# backplane_rev_2.net
KiCad netlist of a schematic drawn in EAGLE
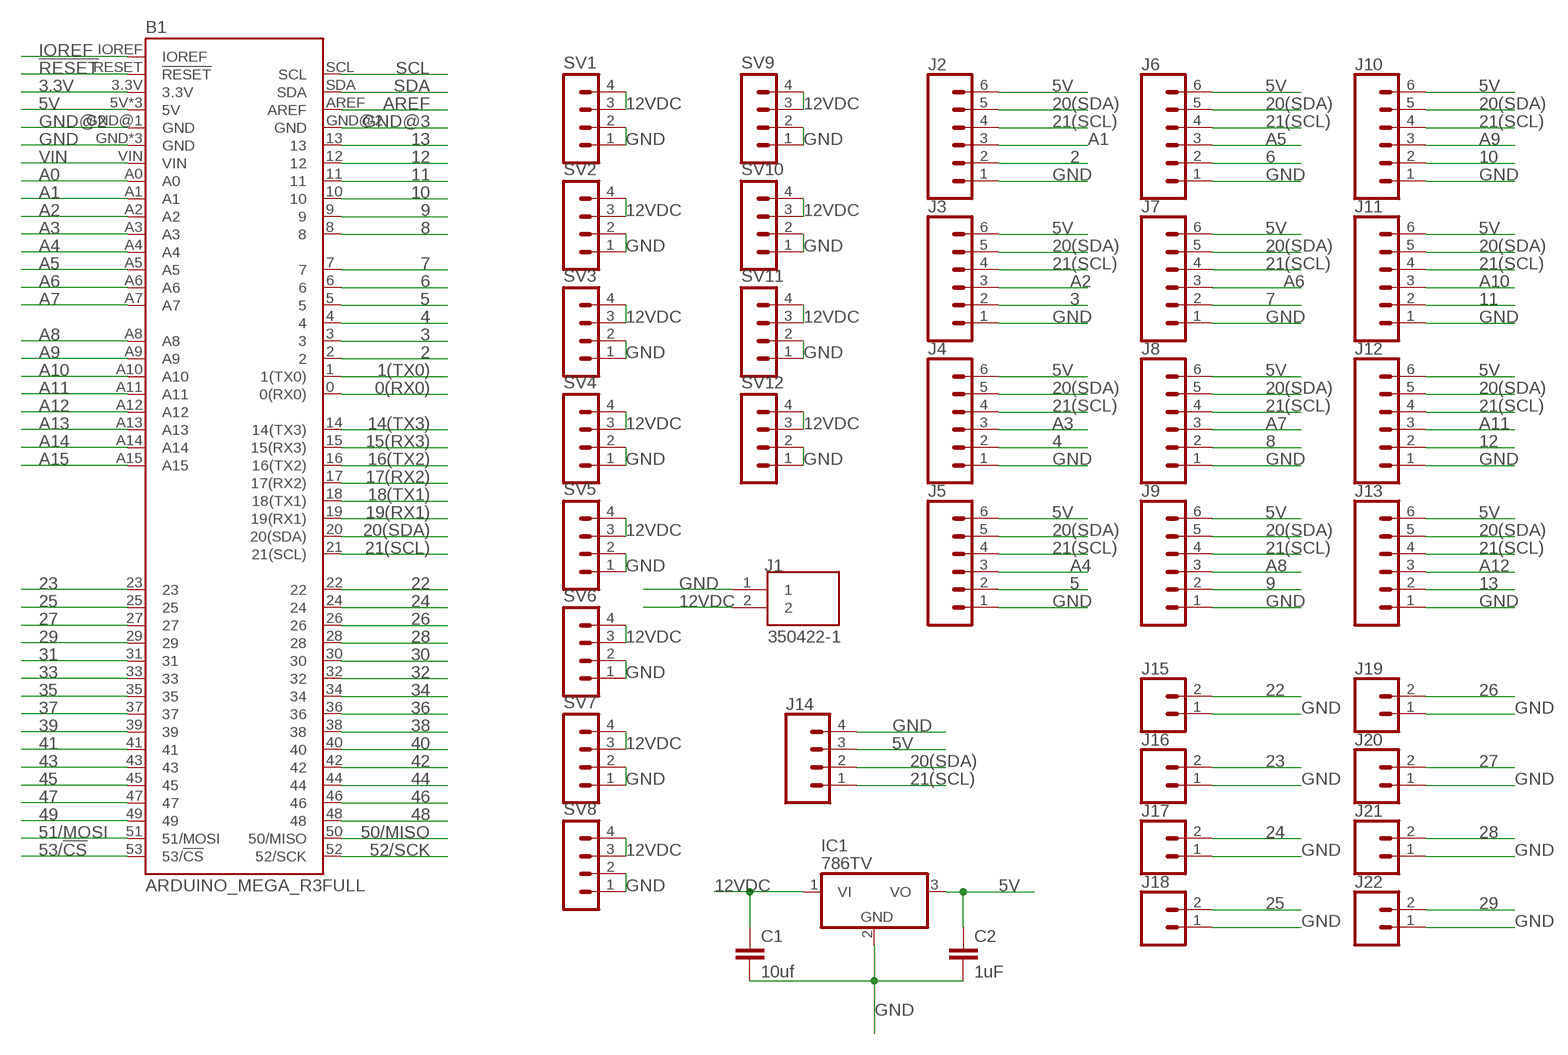
[diagram p0: schematic, sheet 1]

(export (version "E")
  (design (tool "Eeschema 10.0.6"))
  (components
    (comp (ref "B1")
      (value "ARDUINO_MEGA_R3FULL")
      (footprint "eagle-import:ARDUINO_MEGA_NO_SILK")
      (libsource (lib "eagle-import") (part "ARDUINO_MEGA_R3FULL"))
    )
    (comp (ref "C1")
      (value "10uf")
      (footprint "eagle-import:C2.5-3")
      (libsource (lib "eagle-import") (part "C2,5-3"))
    )
    (comp (ref "C2")
      (value "1uF")
      (footprint "eagle-import:C2.5-3")
      (libsource (lib "eagle-import") (part "C2,5-3"))
    )
    (comp (ref "IC1")
      (value "786TV")
      (footprint "eagle-import:TO220V")
      (libsource (lib "eagle-import") (part "78TV6"))
    )
    (comp (ref "J1")
      (value "350422-1")
      (footprint "eagle-import:POWER-PIN")
      (fields (field (name "DIGI-KEY_PART_NUMBER") "A14367-ND") (field (name "MF") "TE Connectivity"))
      (libsource (lib "eagle-import") (part "350422-1"))
    )
    (comp (ref "J2")
      (value "CONN_06NO_SILK_FEMALE_PTH")
      (footprint "eagle-import:1X06_NO_SILK")
      (libsource (lib "eagle-import") (part "CONN_06NO_SILK_FEMALE_PTH"))
    )
    (comp (ref "J3")
      (value "CONN_06NO_SILK_FEMALE_PTH")
      (footprint "eagle-import:1X06_NO_SILK")
      (libsource (lib "eagle-import") (part "CONN_06NO_SILK_FEMALE_PTH"))
    )
    (comp (ref "J4")
      (value "CONN_06NO_SILK_FEMALE_PTH")
      (footprint "eagle-import:1X06_NO_SILK")
      (libsource (lib "eagle-import") (part "CONN_06NO_SILK_FEMALE_PTH"))
    )
    (comp (ref "J5")
      (value "CONN_06NO_SILK_FEMALE_PTH")
      (footprint "eagle-import:1X06_NO_SILK")
      (libsource (lib "eagle-import") (part "CONN_06NO_SILK_FEMALE_PTH"))
    )
    (comp (ref "J6")
      (value "CONN_06NO_SILK_FEMALE_PTH")
      (footprint "eagle-import:1X06_NO_SILK")
      (libsource (lib "eagle-import") (part "CONN_06NO_SILK_FEMALE_PTH"))
    )
    (comp (ref "J7")
      (value "CONN_06NO_SILK_FEMALE_PTH")
      (footprint "eagle-import:1X06_NO_SILK")
      (libsource (lib "eagle-import") (part "CONN_06NO_SILK_FEMALE_PTH"))
    )
    (comp (ref "J8")
      (value "CONN_06NO_SILK_FEMALE_PTH")
      (footprint "eagle-import:1X06_NO_SILK")
      (libsource (lib "eagle-import") (part "CONN_06NO_SILK_FEMALE_PTH"))
    )
    (comp (ref "J9")
      (value "CONN_06NO_SILK_FEMALE_PTH")
      (footprint "eagle-import:1X06_NO_SILK")
      (libsource (lib "eagle-import") (part "CONN_06NO_SILK_FEMALE_PTH"))
    )
    (comp (ref "J10")
      (value "CONN_06NO_SILK_FEMALE_PTH")
      (footprint "eagle-import:1X06_NO_SILK")
      (libsource (lib "eagle-import") (part "CONN_06NO_SILK_FEMALE_PTH"))
    )
    (comp (ref "J11")
      (value "CONN_06NO_SILK_FEMALE_PTH")
      (footprint "eagle-import:1X06_NO_SILK")
      (libsource (lib "eagle-import") (part "CONN_06NO_SILK_FEMALE_PTH"))
    )
    (comp (ref "J12")
      (value "CONN_06NO_SILK_FEMALE_PTH")
      (footprint "eagle-import:1X06_NO_SILK")
      (libsource (lib "eagle-import") (part "CONN_06NO_SILK_FEMALE_PTH"))
    )
    (comp (ref "J13")
      (value "CONN_06NO_SILK_FEMALE_PTH")
      (footprint "eagle-import:1X06_NO_SILK")
      (libsource (lib "eagle-import") (part "CONN_06NO_SILK_FEMALE_PTH"))
    )
    (comp (ref "J14")
      (value "CONN_04PTH")
      (footprint "eagle-import:1X04")
      (libsource (lib "eagle-import") (part "CONN_04PTH"))
    )
    (comp (ref "J15")
      (value "CONN_02")
      (footprint "eagle-import:1X02")
      (libsource (lib "eagle-import") (part "CONN_02"))
    )
    (comp (ref "J16")
      (value "CONN_02")
      (footprint "eagle-import:1X02")
      (libsource (lib "eagle-import") (part "CONN_02"))
    )
    (comp (ref "J17")
      (value "CONN_02")
      (footprint "eagle-import:1X02")
      (libsource (lib "eagle-import") (part "CONN_02"))
    )
    (comp (ref "J18")
      (value "CONN_02")
      (footprint "eagle-import:1X02")
      (libsource (lib "eagle-import") (part "CONN_02"))
    )
    (comp (ref "J19")
      (value "CONN_02")
      (footprint "eagle-import:1X02")
      (libsource (lib "eagle-import") (part "CONN_02"))
    )
    (comp (ref "J20")
      (value "CONN_02")
      (footprint "eagle-import:1X02")
      (libsource (lib "eagle-import") (part "CONN_02"))
    )
    (comp (ref "J21")
      (value "CONN_02")
      (footprint "eagle-import:1X02")
      (libsource (lib "eagle-import") (part "CONN_02"))
    )
    (comp (ref "J22")
      (value "CONN_02")
      (footprint "eagle-import:1X02")
      (libsource (lib "eagle-import") (part "CONN_02"))
    )
    (comp (ref "SV1")
      (value "MA04-1")
      (footprint "eagle-import:MA04-1")
      (libsource (lib "eagle-import") (part "MA04-1"))
    )
    (comp (ref "SV2")
      (value "MA04-1")
      (footprint "eagle-import:MA04-1")
      (libsource (lib "eagle-import") (part "MA04-1"))
    )
    (comp (ref "SV3")
      (value "MA04-1")
      (footprint "eagle-import:MA04-1")
      (libsource (lib "eagle-import") (part "MA04-1"))
    )
    (comp (ref "SV4")
      (value "MA04-1")
      (footprint "eagle-import:MA04-1")
      (libsource (lib "eagle-import") (part "MA04-1"))
    )
    (comp (ref "SV5")
      (value "MA04-1")
      (footprint "eagle-import:MA04-1")
      (libsource (lib "eagle-import") (part "MA04-1"))
    )
    (comp (ref "SV6")
      (value "MA04-1")
      (footprint "eagle-import:MA04-1")
      (libsource (lib "eagle-import") (part "MA04-1"))
    )
    (comp (ref "SV7")
      (value "MA04-1")
      (footprint "eagle-import:MA04-1")
      (libsource (lib "eagle-import") (part "MA04-1"))
    )
    (comp (ref "SV8")
      (value "MA04-1")
      (footprint "eagle-import:MA04-1")
      (libsource (lib "eagle-import") (part "MA04-1"))
    )
    (comp (ref "SV9")
      (value "MA04-1")
      (footprint "eagle-import:MA04-1")
      (libsource (lib "eagle-import") (part "MA04-1"))
    )
    (comp (ref "SV10")
      (value "MA04-1")
      (footprint "eagle-import:MA04-1")
      (libsource (lib "eagle-import") (part "MA04-1"))
    )
    (comp (ref "SV11")
      (value "MA04-1")
      (footprint "eagle-import:MA04-1")
      (libsource (lib "eagle-import") (part "MA04-1"))
    )
    (comp (ref "SV12")
      (value "MA04-1")
      (footprint "eagle-import:MA04-1")
      (libsource (lib "eagle-import") (part "MA04-1"))
    )
  )
  (nets
    (net (code "1") (name "/0(RX0)") (class "Default")
      (node (ref "B1") (pin "0") (pinfunction "0(RX0)_0") (pintype "bidirectional"))
    )
    (net (code "2") (name "/1(TX0)") (class "Default")
      (node (ref "B1") (pin "1") (pinfunction "1(TX0)_1") (pintype "bidirectional"))
    )
    (net (code "3") (name "/2") (class "Default")
      (node (ref "B1") (pin "2") (pinfunction "2_2") (pintype "bidirectional"))
      (node (ref "J2") (pin "2") (pinfunction "2_2") (pintype "passive"))
    )
    (net (code "4") (name "/3") (class "Default")
      (node (ref "B1") (pin "3") (pinfunction "3_3") (pintype "bidirectional"))
      (node (ref "J3") (pin "2") (pinfunction "2_2") (pintype "passive"))
    )
    (net (code "5") (name "/3.3V") (class "Default")
      (node (ref "B1") (pin "3.3V") (pinfunction "3.3V_3.3V") (pintype "bidirectional"))
    )
    (net (code "6") (name "/4") (class "Default")
      (node (ref "B1") (pin "4") (pinfunction "4_4") (pintype "bidirectional"))
      (node (ref "J4") (pin "2") (pinfunction "2_2") (pintype "passive"))
    )
    (net (code "7") (name "/5") (class "Default")
      (node (ref "B1") (pin "5") (pinfunction "5_5") (pintype "bidirectional"))
      (node (ref "J5") (pin "2") (pinfunction "2_2") (pintype "passive"))
    )
    (net (code "8") (name "/5V") (class "Default")
      (node (ref "B1") (pin "5V") (pinfunction "5V_5V") (pintype "bidirectional"))
      (node (ref "B1") (pin "5V@1") (pinfunction "5V_5V@1") (pintype "bidirectional"))
      (node (ref "B1") (pin "5V@2") (pinfunction "5V_5V@2") (pintype "bidirectional"))
      (node (ref "C2") (pin "1") (pinfunction "1_1") (pintype "passive"))
      (node (ref "IC1") (pin "3") (pinfunction "VO_3") (pintype "passive"))
      (node (ref "J10") (pin "6") (pinfunction "6_6") (pintype "passive"))
      (node (ref "J11") (pin "6") (pinfunction "6_6") (pintype "passive"))
      (node (ref "J12") (pin "6") (pinfunction "6_6") (pintype "passive"))
      (node (ref "J13") (pin "6") (pinfunction "6_6") (pintype "passive"))
      (node (ref "J14") (pin "3") (pinfunction "3_3") (pintype "passive"))
      (node (ref "J2") (pin "6") (pinfunction "6_6") (pintype "passive"))
      (node (ref "J3") (pin "6") (pinfunction "6_6") (pintype "passive"))
      (node (ref "J4") (pin "6") (pinfunction "6_6") (pintype "passive"))
      (node (ref "J5") (pin "6") (pinfunction "6_6") (pintype "passive"))
      (node (ref "J6") (pin "6") (pinfunction "6_6") (pintype "passive"))
      (node (ref "J7") (pin "6") (pinfunction "6_6") (pintype "passive"))
      (node (ref "J8") (pin "6") (pinfunction "6_6") (pintype "passive"))
      (node (ref "J9") (pin "6") (pinfunction "6_6") (pintype "passive"))
    )
    (net (code "9") (name "/6") (class "Default")
      (node (ref "B1") (pin "6") (pinfunction "6_6") (pintype "bidirectional"))
      (node (ref "J6") (pin "2") (pinfunction "2_2") (pintype "passive"))
    )
    (net (code "10") (name "/7") (class "Default")
      (node (ref "B1") (pin "7") (pinfunction "7_7") (pintype "bidirectional"))
      (node (ref "J7") (pin "2") (pinfunction "2_2") (pintype "passive"))
    )
    (net (code "11") (name "/8") (class "Default")
      (node (ref "B1") (pin "8") (pinfunction "8_8") (pintype "bidirectional"))
      (node (ref "J8") (pin "2") (pinfunction "2_2") (pintype "passive"))
    )
    (net (code "12") (name "/9") (class "Default")
      (node (ref "B1") (pin "9") (pinfunction "9_9") (pintype "bidirectional"))
      (node (ref "J9") (pin "2") (pinfunction "2_2") (pintype "passive"))
    )
    (net (code "13") (name "/10") (class "Default")
      (node (ref "B1") (pin "10") (pinfunction "10_10") (pintype "bidirectional"))
      (node (ref "J10") (pin "2") (pinfunction "2_2") (pintype "passive"))
    )
    (net (code "14") (name "/11") (class "Default")
      (node (ref "B1") (pin "11") (pinfunction "11_11") (pintype "bidirectional"))
      (node (ref "J11") (pin "2") (pinfunction "2_2") (pintype "passive"))
    )
    (net (code "15") (name "/12") (class "Default")
      (node (ref "B1") (pin "12") (pinfunction "12_12") (pintype "bidirectional"))
      (node (ref "J12") (pin "2") (pinfunction "2_2") (pintype "passive"))
    )
    (net (code "16") (name "/12VDC") (class "Default")
      (node (ref "C1") (pin "1") (pinfunction "1_1") (pintype "passive"))
      (node (ref "IC1") (pin "1") (pinfunction "VI_1") (pintype "input"))
      (node (ref "J1") (pin "2") (pinfunction "2_2") (pintype "passive"))
      (node (ref "SV1") (pin "3") (pinfunction "3_3") (pintype "passive"))
      (node (ref "SV1") (pin "4") (pinfunction "4_4") (pintype "passive"))
      (node (ref "SV10") (pin "3") (pinfunction "3_3") (pintype "passive"))
      (node (ref "SV10") (pin "4") (pinfunction "4_4") (pintype "passive"))
      (node (ref "SV11") (pin "3") (pinfunction "3_3") (pintype "passive"))
      (node (ref "SV11") (pin "4") (pinfunction "4_4") (pintype "passive"))
      (node (ref "SV12") (pin "3") (pinfunction "3_3") (pintype "passive"))
      (node (ref "SV12") (pin "4") (pinfunction "4_4") (pintype "passive"))
      (node (ref "SV2") (pin "3") (pinfunction "3_3") (pintype "passive"))
      (node (ref "SV2") (pin "4") (pinfunction "4_4") (pintype "passive"))
      (node (ref "SV3") (pin "3") (pinfunction "3_3") (pintype "passive"))
      (node (ref "SV3") (pin "4") (pinfunction "4_4") (pintype "passive"))
      (node (ref "SV4") (pin "3") (pinfunction "3_3") (pintype "passive"))
      (node (ref "SV4") (pin "4") (pinfunction "4_4") (pintype "passive"))
      (node (ref "SV5") (pin "3") (pinfunction "3_3") (pintype "passive"))
      (node (ref "SV5") (pin "4") (pinfunction "4_4") (pintype "passive"))
      (node (ref "SV6") (pin "3") (pinfunction "3_3") (pintype "passive"))
      (node (ref "SV6") (pin "4") (pinfunction "4_4") (pintype "passive"))
      (node (ref "SV7") (pin "3") (pinfunction "3_3") (pintype "passive"))
      (node (ref "SV7") (pin "4") (pinfunction "4_4") (pintype "passive"))
      (node (ref "SV8") (pin "3") (pinfunction "3_3") (pintype "passive"))
      (node (ref "SV8") (pin "4") (pinfunction "4_4") (pintype "passive"))
      (node (ref "SV9") (pin "3") (pinfunction "3_3") (pintype "passive"))
      (node (ref "SV9") (pin "4") (pinfunction "4_4") (pintype "passive"))
    )
    (net (code "17") (name "/13") (class "Default")
      (node (ref "B1") (pin "13") (pinfunction "13_13") (pintype "bidirectional"))
      (node (ref "J13") (pin "2") (pinfunction "2_2") (pintype "passive"))
    )
    (net (code "18") (name "/14(TX3)") (class "Default")
      (node (ref "B1") (pin "14") (pinfunction "14(TX3)_14") (pintype "bidirectional"))
    )
    (net (code "19") (name "/15(RX3)") (class "Default")
      (node (ref "B1") (pin "15") (pinfunction "15(RX3)_15") (pintype "bidirectional"))
    )
    (net (code "20") (name "/16(TX2)") (class "Default")
      (node (ref "B1") (pin "16") (pinfunction "16(TX2)_16") (pintype "bidirectional"))
    )
    (net (code "21") (name "/17(RX2)") (class "Default")
      (node (ref "B1") (pin "17") (pinfunction "17(RX2)_17") (pintype "bidirectional"))
    )
    (net (code "22") (name "/18(TX1)") (class "Default")
      (node (ref "B1") (pin "18") (pinfunction "18(TX1)_18") (pintype "bidirectional"))
    )
    (net (code "23") (name "/19(RX1)") (class "Default")
      (node (ref "B1") (pin "19") (pinfunction "19(RX1)_19") (pintype "bidirectional"))
    )
    (net (code "24") (name "/20(SDA)") (class "Default")
      (node (ref "B1") (pin "20") (pinfunction "20(SDA)_20") (pintype "bidirectional"))
      (node (ref "J10") (pin "5") (pinfunction "5_5") (pintype "passive"))
      (node (ref "J11") (pin "5") (pinfunction "5_5") (pintype "passive"))
      (node (ref "J12") (pin "5") (pinfunction "5_5") (pintype "passive"))
      (node (ref "J13") (pin "5") (pinfunction "5_5") (pintype "passive"))
      (node (ref "J14") (pin "2") (pinfunction "2_2") (pintype "passive"))
      (node (ref "J2") (pin "5") (pinfunction "5_5") (pintype "passive"))
      (node (ref "J3") (pin "5") (pinfunction "5_5") (pintype "passive"))
      (node (ref "J4") (pin "5") (pinfunction "5_5") (pintype "passive"))
      (node (ref "J5") (pin "5") (pinfunction "5_5") (pintype "passive"))
      (node (ref "J6") (pin "5") (pinfunction "5_5") (pintype "passive"))
      (node (ref "J7") (pin "5") (pinfunction "5_5") (pintype "passive"))
      (node (ref "J8") (pin "5") (pinfunction "5_5") (pintype "passive"))
      (node (ref "J9") (pin "5") (pinfunction "5_5") (pintype "passive"))
    )
    (net (code "25") (name "/21(SCL)") (class "Default")
      (node (ref "B1") (pin "21") (pinfunction "21(SCL)_21") (pintype "bidirectional"))
      (node (ref "J10") (pin "4") (pinfunction "4_4") (pintype "passive"))
      (node (ref "J11") (pin "4") (pinfunction "4_4") (pintype "passive"))
      (node (ref "J12") (pin "4") (pinfunction "4_4") (pintype "passive"))
      (node (ref "J13") (pin "4") (pinfunction "4_4") (pintype "passive"))
      (node (ref "J14") (pin "1") (pinfunction "1_1") (pintype "passive"))
      (node (ref "J2") (pin "4") (pinfunction "4_4") (pintype "passive"))
      (node (ref "J3") (pin "4") (pinfunction "4_4") (pintype "passive"))
      (node (ref "J4") (pin "4") (pinfunction "4_4") (pintype "passive"))
      (node (ref "J5") (pin "4") (pinfunction "4_4") (pintype "passive"))
      (node (ref "J6") (pin "4") (pinfunction "4_4") (pintype "passive"))
      (node (ref "J7") (pin "4") (pinfunction "4_4") (pintype "passive"))
      (node (ref "J8") (pin "4") (pinfunction "4_4") (pintype "passive"))
      (node (ref "J9") (pin "4") (pinfunction "4_4") (pintype "passive"))
    )
    (net (code "26") (name "/22") (class "Default")
      (node (ref "B1") (pin "22") (pinfunction "22_22") (pintype "bidirectional"))
      (node (ref "J15") (pin "2") (pinfunction "2_2") (pintype "passive"))
    )
    (net (code "27") (name "/23") (class "Default")
      (node (ref "B1") (pin "23") (pinfunction "23_23") (pintype "bidirectional"))
      (node (ref "J16") (pin "2") (pinfunction "2_2") (pintype "passive"))
    )
    (net (code "28") (name "/24") (class "Default")
      (node (ref "B1") (pin "24") (pinfunction "24_24") (pintype "bidirectional"))
      (node (ref "J17") (pin "2") (pinfunction "2_2") (pintype "passive"))
    )
    (net (code "29") (name "/25") (class "Default")
      (node (ref "B1") (pin "25") (pinfunction "25_25") (pintype "bidirectional"))
      (node (ref "J18") (pin "2") (pinfunction "2_2") (pintype "passive"))
    )
    (net (code "30") (name "/26") (class "Default")
      (node (ref "B1") (pin "26") (pinfunction "26_26") (pintype "bidirectional"))
      (node (ref "J19") (pin "2") (pinfunction "2_2") (pintype "passive"))
    )
    (net (code "31") (name "/27") (class "Default")
      (node (ref "B1") (pin "27") (pinfunction "27_27") (pintype "bidirectional"))
      (node (ref "J20") (pin "2") (pinfunction "2_2") (pintype "passive"))
    )
    (net (code "32") (name "/28") (class "Default")
      (node (ref "B1") (pin "28") (pinfunction "28_28") (pintype "bidirectional"))
      (node (ref "J21") (pin "2") (pinfunction "2_2") (pintype "passive"))
    )
    (net (code "33") (name "/29") (class "Default")
      (node (ref "B1") (pin "29") (pinfunction "29_29") (pintype "bidirectional"))
      (node (ref "J22") (pin "2") (pinfunction "2_2") (pintype "passive"))
    )
    (net (code "34") (name "/30") (class "Default")
      (node (ref "B1") (pin "30") (pinfunction "30_30") (pintype "bidirectional"))
    )
    (net (code "35") (name "/31") (class "Default")
      (node (ref "B1") (pin "31") (pinfunction "31_31") (pintype "bidirectional"))
    )
    (net (code "36") (name "/32") (class "Default")
      (node (ref "B1") (pin "32") (pinfunction "32_32") (pintype "bidirectional"))
    )
    (net (code "37") (name "/33") (class "Default")
      (node (ref "B1") (pin "33") (pinfunction "33_33") (pintype "bidirectional"))
    )
    (net (code "38") (name "/34") (class "Default")
      (node (ref "B1") (pin "34") (pinfunction "34_34") (pintype "bidirectional"))
    )
    (net (code "39") (name "/35") (class "Default")
      (node (ref "B1") (pin "35") (pinfunction "35_35") (pintype "bidirectional"))
    )
    (net (code "40") (name "/36") (class "Default")
      (node (ref "B1") (pin "36") (pinfunction "36_36") (pintype "bidirectional"))
    )
    (net (code "41") (name "/37") (class "Default")
      (node (ref "B1") (pin "37") (pinfunction "37_37") (pintype "bidirectional"))
    )
    (net (code "42") (name "/38") (class "Default")
      (node (ref "B1") (pin "38") (pinfunction "38_38") (pintype "bidirectional"))
    )
    (net (code "43") (name "/39") (class "Default")
      (node (ref "B1") (pin "39") (pinfunction "39_39") (pintype "bidirectional"))
    )
    (net (code "44") (name "/40") (class "Default")
      (node (ref "B1") (pin "40") (pinfunction "40_40") (pintype "bidirectional"))
    )
    (net (code "45") (name "/41") (class "Default")
      (node (ref "B1") (pin "41") (pinfunction "41_41") (pintype "bidirectional"))
    )
    (net (code "46") (name "/42") (class "Default")
      (node (ref "B1") (pin "42") (pinfunction "42_42") (pintype "bidirectional"))
    )
    (net (code "47") (name "/43") (class "Default")
      (node (ref "B1") (pin "43") (pinfunction "43_43") (pintype "bidirectional"))
    )
    (net (code "48") (name "/44") (class "Default")
      (node (ref "B1") (pin "44") (pinfunction "44_44") (pintype "bidirectional"))
    )
    (net (code "49") (name "/45") (class "Default")
      (node (ref "B1") (pin "45") (pinfunction "45_45") (pintype "bidirectional"))
    )
    (net (code "50") (name "/46") (class "Default")
      (node (ref "B1") (pin "46") (pinfunction "46_46") (pintype "bidirectional"))
    )
    (net (code "51") (name "/47") (class "Default")
      (node (ref "B1") (pin "47") (pinfunction "47_47") (pintype "bidirectional"))
    )
    (net (code "52") (name "/48") (class "Default")
      (node (ref "B1") (pin "48") (pinfunction "48_48") (pintype "bidirectional"))
    )
    (net (code "53") (name "/49") (class "Default")
      (node (ref "B1") (pin "49") (pinfunction "49_49") (pintype "bidirectional"))
    )
    (net (code "54") (name "/50{slash}MISO") (class "Default")
      (node (ref "B1") (pin "50") (pinfunction "50/MISO_50") (pintype "bidirectional"))
    )
    (net (code "55") (name "/51{slash}MOSI") (class "Default")
      (node (ref "B1") (pin "51") (pinfunction "51/MOSI_51") (pintype "bidirectional"))
    )
    (net (code "56") (name "/52{slash}SCK") (class "Default")
      (node (ref "B1") (pin "52") (pinfunction "52/SCK_52") (pintype "bidirectional"))
    )
    (net (code "57") (name "/53{slash}~{CS}") (class "Default")
      (node (ref "B1") (pin "53") (pinfunction "53/~{CS}_53") (pintype "bidirectional"))
    )
    (net (code "58") (name "/A0") (class "Default")
      (node (ref "B1") (pin "A0") (pinfunction "A0_A0") (pintype "bidirectional"))
    )
    (net (code "59") (name "/A1") (class "Default")
      (node (ref "B1") (pin "A1") (pinfunction "A1_A1") (pintype "bidirectional"))
      (node (ref "J2") (pin "3") (pinfunction "3_3") (pintype "passive"))
    )
    (net (code "60") (name "/A2") (class "Default")
      (node (ref "B1") (pin "A2") (pinfunction "A2_A2") (pintype "bidirectional"))
      (node (ref "J3") (pin "3") (pinfunction "3_3") (pintype "passive"))
    )
    (net (code "61") (name "/A3") (class "Default")
      (node (ref "B1") (pin "A3") (pinfunction "A3_A3") (pintype "bidirectional"))
      (node (ref "J4") (pin "3") (pinfunction "3_3") (pintype "passive"))
    )
    (net (code "62") (name "/A4") (class "Default")
      (node (ref "B1") (pin "A4") (pinfunction "A4_A4") (pintype "bidirectional"))
      (node (ref "J5") (pin "3") (pinfunction "3_3") (pintype "passive"))
    )
    (net (code "63") (name "/A5") (class "Default")
      (node (ref "B1") (pin "A5") (pinfunction "A5_A5") (pintype "bidirectional"))
      (node (ref "J6") (pin "3") (pinfunction "3_3") (pintype "passive"))
    )
    (net (code "64") (name "/A6") (class "Default")
      (node (ref "B1") (pin "A6") (pinfunction "A6_A6") (pintype "bidirectional"))
      (node (ref "J7") (pin "3") (pinfunction "3_3") (pintype "passive"))
    )
    (net (code "65") (name "/A7") (class "Default")
      (node (ref "B1") (pin "A7") (pinfunction "A7_A7") (pintype "bidirectional"))
      (node (ref "J8") (pin "3") (pinfunction "3_3") (pintype "passive"))
    )
    (net (code "66") (name "/A8") (class "Default")
      (node (ref "B1") (pin "A8") (pinfunction "A8_A8") (pintype "bidirectional"))
      (node (ref "J9") (pin "3") (pinfunction "3_3") (pintype "passive"))
    )
    (net (code "67") (name "/A9") (class "Default")
      (node (ref "B1") (pin "A9") (pinfunction "A9_A9") (pintype "bidirectional"))
      (node (ref "J10") (pin "3") (pinfunction "3_3") (pintype "passive"))
    )
    (net (code "68") (name "/A10") (class "Default")
      (node (ref "B1") (pin "A10") (pinfunction "A10_A10") (pintype "bidirectional"))
      (node (ref "J11") (pin "3") (pinfunction "3_3") (pintype "passive"))
    )
    (net (code "69") (name "/A11") (class "Default")
      (node (ref "B1") (pin "A11") (pinfunction "A11_A11") (pintype "bidirectional"))
      (node (ref "J12") (pin "3") (pinfunction "3_3") (pintype "passive"))
    )
    (net (code "70") (name "/A12") (class "Default")
      (node (ref "B1") (pin "A12") (pinfunction "A12_A12") (pintype "bidirectional"))
      (node (ref "J13") (pin "3") (pinfunction "3_3") (pintype "passive"))
    )
    (net (code "71") (name "/A13") (class "Default")
      (node (ref "B1") (pin "A13") (pinfunction "A13_A13") (pintype "bidirectional"))
    )
    (net (code "72") (name "/A14") (class "Default")
      (node (ref "B1") (pin "A14") (pinfunction "A14_A14") (pintype "bidirectional"))
    )
    (net (code "73") (name "/A15") (class "Default")
      (node (ref "B1") (pin "A15") (pinfunction "A15_A15") (pintype "bidirectional"))
    )
    (net (code "74") (name "/AREF") (class "Default")
      (node (ref "B1") (pin "AREF") (pinfunction "AREF_AREF") (pintype "bidirectional"))
    )
    (net (code "75") (name "/GND") (class "Default")
      (node (ref "B1") (pin "GND") (pinfunction "GND_GND") (pintype "bidirectional"))
      (node (ref "B1") (pin "GND@3") (pinfunction "GND_GND@3") (pintype "bidirectional"))
      (node (ref "B1") (pin "GND@4") (pinfunction "GND_GND@4") (pintype "bidirectional"))
      (node (ref "C1") (pin "2") (pinfunction "2_2") (pintype "passive"))
      (node (ref "C2") (pin "2") (pinfunction "2_2") (pintype "passive"))
      (node (ref "IC1") (pin "2") (pinfunction "GND_2") (pintype "passive"))
      (node (ref "J1") (pin "1") (pinfunction "1_1") (pintype "passive"))
      (node (ref "J10") (pin "1") (pinfunction "1_1") (pintype "passive"))
      (node (ref "J11") (pin "1") (pinfunction "1_1") (pintype "passive"))
      (node (ref "J12") (pin "1") (pinfunction "1_1") (pintype "passive"))
      (node (ref "J13") (pin "1") (pinfunction "1_1") (pintype "passive"))
      (node (ref "J14") (pin "4") (pinfunction "4_4") (pintype "passive"))
      (node (ref "J15") (pin "1") (pinfunction "1_1") (pintype "passive"))
      (node (ref "J16") (pin "1") (pinfunction "1_1") (pintype "passive"))
      (node (ref "J17") (pin "1") (pinfunction "1_1") (pintype "passive"))
      (node (ref "J18") (pin "1") (pinfunction "1_1") (pintype "passive"))
      (node (ref "J19") (pin "1") (pinfunction "1_1") (pintype "passive"))
      (node (ref "J2") (pin "1") (pinfunction "1_1") (pintype "passive"))
      (node (ref "J20") (pin "1") (pinfunction "1_1") (pintype "passive"))
      (node (ref "J21") (pin "1") (pinfunction "1_1") (pintype "passive"))
      (node (ref "J22") (pin "1") (pinfunction "1_1") (pintype "passive"))
      (node (ref "J3") (pin "1") (pinfunction "1_1") (pintype "passive"))
      (node (ref "J4") (pin "1") (pinfunction "1_1") (pintype "passive"))
      (node (ref "J5") (pin "1") (pinfunction "1_1") (pintype "passive"))
      (node (ref "J6") (pin "1") (pinfunction "1_1") (pintype "passive"))
      (node (ref "J7") (pin "1") (pinfunction "1_1") (pintype "passive"))
      (node (ref "J8") (pin "1") (pinfunction "1_1") (pintype "passive"))
      (node (ref "J9") (pin "1") (pinfunction "1_1") (pintype "passive"))
      (node (ref "SV1") (pin "1") (pinfunction "1_1") (pintype "passive"))
      (node (ref "SV1") (pin "2") (pinfunction "2_2") (pintype "passive"))
      (node (ref "SV10") (pin "1") (pinfunction "1_1") (pintype "passive"))
      (node (ref "SV10") (pin "2") (pinfunction "2_2") (pintype "passive"))
      (node (ref "SV11") (pin "1") (pinfunction "1_1") (pintype "passive"))
      (node (ref "SV11") (pin "2") (pinfunction "2_2") (pintype "passive"))
      (node (ref "SV12") (pin "1") (pinfunction "1_1") (pintype "passive"))
      (node (ref "SV12") (pin "2") (pinfunction "2_2") (pintype "passive"))
      (node (ref "SV2") (pin "1") (pinfunction "1_1") (pintype "passive"))
      (node (ref "SV2") (pin "2") (pinfunction "2_2") (pintype "passive"))
      (node (ref "SV3") (pin "1") (pinfunction "1_1") (pintype "passive"))
      (node (ref "SV3") (pin "2") (pinfunction "2_2") (pintype "passive"))
      (node (ref "SV4") (pin "1") (pinfunction "1_1") (pintype "passive"))
      (node (ref "SV4") (pin "2") (pinfunction "2_2") (pintype "passive"))
      (node (ref "SV5") (pin "1") (pinfunction "1_1") (pintype "passive"))
      (node (ref "SV5") (pin "2") (pinfunction "2_2") (pintype "passive"))
      (node (ref "SV6") (pin "1") (pinfunction "1_1") (pintype "passive"))
      (node (ref "SV6") (pin "2") (pinfunction "2_2") (pintype "passive"))
      (node (ref "SV7") (pin "1") (pinfunction "1_1") (pintype "passive"))
      (node (ref "SV7") (pin "2") (pinfunction "2_2") (pintype "passive"))
      (node (ref "SV8") (pin "1") (pinfunction "1_1") (pintype "passive"))
      (node (ref "SV8") (pin "2") (pinfunction "2_2") (pintype "passive"))
      (node (ref "SV9") (pin "1") (pinfunction "1_1") (pintype "passive"))
      (node (ref "SV9") (pin "2") (pinfunction "2_2") (pintype "passive"))
    )
    (net (code "76") (name "/GND@2") (class "Default")
      (node (ref "B1") (pin "GND@1") (pinfunction "GND_GND@1") (pintype "bidirectional"))
    )
    (net (code "77") (name "/GND@3") (class "Default")
      (node (ref "B1") (pin "GND@2") (pinfunction "GND_GND@2") (pintype "bidirectional"))
    )
    (net (code "78") (name "/IOREF") (class "Default")
      (node (ref "B1") (pin "IOREF") (pinfunction "IOREF_IOREF") (pintype "bidirectional"))
    )
    (net (code "79") (name "/SCL") (class "Default")
      (node (ref "B1") (pin "SCL") (pinfunction "SCL_SCL") (pintype "bidirectional"))
    )
    (net (code "80") (name "/SDA") (class "Default")
      (node (ref "B1") (pin "SDA") (pinfunction "SDA_SDA") (pintype "bidirectional"))
    )
    (net (code "81") (name "/VIN") (class "Default")
      (node (ref "B1") (pin "VIN") (pinfunction "VIN_VIN") (pintype "bidirectional"))
    )
    (net (code "82") (name "/~{RESET}") (class "Default")
      (node (ref "B1") (pin "RESET") (pinfunction "~{RESET}_RESET") (pintype "bidirectional"))
    )
  )
)
